# i2c_arduino.net
KiCad netlist of a schematic drawn in EAGLE
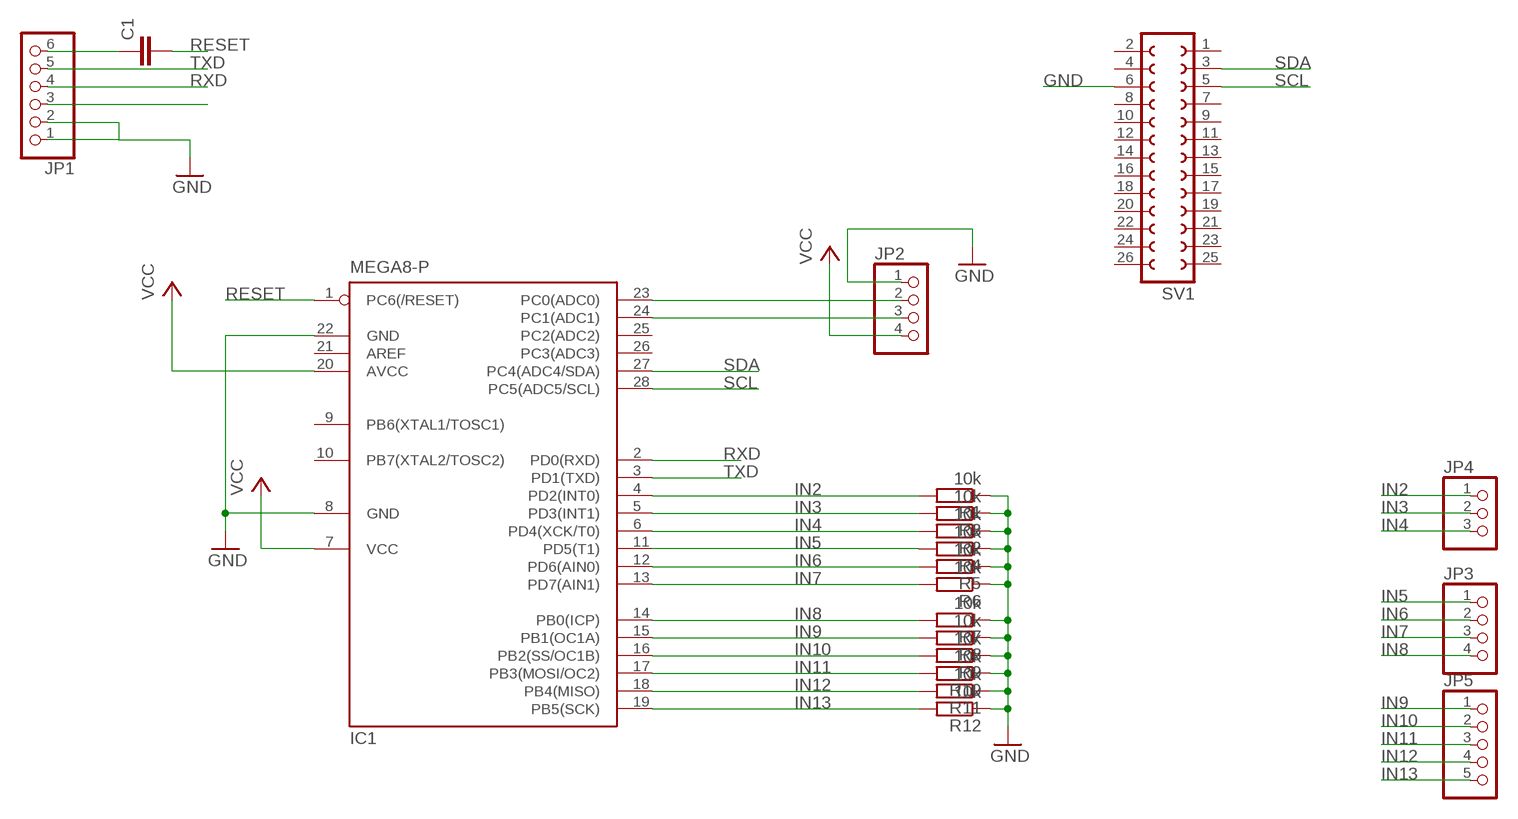
[diagram p0: schematic, sheet 1]

(export (version "E")
  (design (tool "Eeschema 10.0.6"))
  (components
    (comp (ref "C1")
      (value "C-EU025-025X050")
      (footprint "eagle-import:C025-025X050")
      (libsource (lib "eagle-import") (part "C-EU025-025X050"))
    )
    (comp (ref "IC1")
      (value "MEGA8-P")
      (footprint "eagle-import:DIL28-3")
      (libsource (lib "eagle-import") (part "MEGA8-P"))
    )
    (comp (ref "JP1")
      (value "PINHD-1X6/90")
      (footprint "eagle-import:1X06_90")
      (libsource (lib "eagle-import") (part "PINHD-1X6/90"))
    )
    (comp (ref "JP2")
      (value "PINHD-1X4")
      (footprint "eagle-import:1X04")
      (libsource (lib "eagle-import") (part "PINHD-1X4"))
    )
    (comp (ref "JP3")
      (value "PINHD-1X4")
      (footprint "eagle-import:1X04")
      (libsource (lib "eagle-import") (part "PINHD-1X4"))
    )
    (comp (ref "JP4")
      (value "PINHD-1X3")
      (footprint "eagle-import:1X03")
      (libsource (lib "eagle-import") (part "PINHD-1X3"))
    )
    (comp (ref "JP5")
      (value "PINHD-1X5")
      (footprint "eagle-import:1X05")
      (libsource (lib "eagle-import") (part "PINHD-1X5"))
    )
    (comp (ref "R1")
      (value "10k")
      (footprint "eagle-import:M1206")
      (libsource (lib "eagle-import") (part "R-EU_M1206"))
    )
    (comp (ref "R2")
      (value "10k")
      (footprint "eagle-import:M1206")
      (libsource (lib "eagle-import") (part "R-EU_M1206"))
    )
    (comp (ref "R3")
      (value "10k")
      (footprint "eagle-import:M1206")
      (libsource (lib "eagle-import") (part "R-EU_M1206"))
    )
    (comp (ref "R4")
      (value "10k")
      (footprint "eagle-import:M1206")
      (libsource (lib "eagle-import") (part "R-EU_M1206"))
    )
    (comp (ref "R5")
      (value "10k")
      (footprint "eagle-import:M1206")
      (libsource (lib "eagle-import") (part "R-EU_M1206"))
    )
    (comp (ref "R6")
      (value "10k")
      (footprint "eagle-import:M1206")
      (libsource (lib "eagle-import") (part "R-EU_M1206"))
    )
    (comp (ref "R7")
      (value "10k")
      (footprint "eagle-import:M1206")
      (libsource (lib "eagle-import") (part "R-EU_M1206"))
    )
    (comp (ref "R8")
      (value "10k")
      (footprint "eagle-import:M1206")
      (libsource (lib "eagle-import") (part "R-EU_M1206"))
    )
    (comp (ref "R9")
      (value "10k")
      (footprint "eagle-import:M1206")
      (libsource (lib "eagle-import") (part "R-EU_M1206"))
    )
    (comp (ref "R10")
      (value "10k")
      (footprint "eagle-import:M1206")
      (libsource (lib "eagle-import") (part "R-EU_M1206"))
    )
    (comp (ref "R11")
      (value "10k")
      (footprint "eagle-import:M1206")
      (libsource (lib "eagle-import") (part "R-EU_M1206"))
    )
    (comp (ref "R12")
      (value "10k")
      (footprint "eagle-import:M1206")
      (libsource (lib "eagle-import") (part "R-EU_M1206"))
    )
    (comp (ref "SV1")
      (value "FE13-2")
      (footprint "eagle-import:FE13-2")
      (libsource (lib "eagle-import") (part "FE13-2"))
    )
  )
  (nets
    (net (code "1") (name "/IN2") (class "Default")
      (node (ref "IC1") (pin "4") (pinfunction "PD2(INT0)_4") (pintype "bidirectional"))
      (node (ref "JP4") (pin "1") (pinfunction "1_1") (pintype "passive"))
      (node (ref "R1") (pin "2") (pinfunction "2_2") (pintype "passive"))
    )
    (net (code "2") (name "/IN3") (class "Default")
      (node (ref "IC1") (pin "5") (pinfunction "PD3(INT1)_5") (pintype "bidirectional"))
      (node (ref "JP4") (pin "2") (pinfunction "2_2") (pintype "passive"))
      (node (ref "R3") (pin "2") (pinfunction "2_2") (pintype "passive"))
    )
    (net (code "3") (name "/IN4") (class "Default")
      (node (ref "IC1") (pin "6") (pinfunction "PD4(XCK/T0)_6") (pintype "bidirectional"))
      (node (ref "JP4") (pin "3") (pinfunction "3_3") (pintype "passive"))
      (node (ref "R2") (pin "2") (pinfunction "2_2") (pintype "passive"))
    )
    (net (code "4") (name "/IN5") (class "Default")
      (node (ref "IC1") (pin "11") (pinfunction "PD5(T1)_11") (pintype "bidirectional"))
      (node (ref "JP3") (pin "1") (pinfunction "1_1") (pintype "passive"))
      (node (ref "R4") (pin "2") (pinfunction "2_2") (pintype "passive"))
    )
    (net (code "5") (name "/IN6") (class "Default")
      (node (ref "IC1") (pin "12") (pinfunction "PD6(AIN0)_12") (pintype "bidirectional"))
      (node (ref "JP3") (pin "2") (pinfunction "2_2") (pintype "passive"))
      (node (ref "R5") (pin "2") (pinfunction "2_2") (pintype "passive"))
    )
    (net (code "6") (name "/IN7") (class "Default")
      (node (ref "IC1") (pin "13") (pinfunction "PD7(AIN1)_13") (pintype "bidirectional"))
      (node (ref "JP3") (pin "3") (pinfunction "3_3") (pintype "passive"))
      (node (ref "R6") (pin "2") (pinfunction "2_2") (pintype "passive"))
    )
    (net (code "7") (name "/IN8") (class "Default")
      (node (ref "IC1") (pin "14") (pinfunction "PB0(ICP)_14") (pintype "bidirectional"))
      (node (ref "JP3") (pin "4") (pinfunction "4_4") (pintype "passive"))
      (node (ref "R7") (pin "2") (pinfunction "2_2") (pintype "passive"))
    )
    (net (code "8") (name "/IN9") (class "Default")
      (node (ref "IC1") (pin "15") (pinfunction "PB1(OC1A)_15") (pintype "bidirectional"))
      (node (ref "JP5") (pin "1") (pinfunction "1_1") (pintype "passive"))
      (node (ref "R8") (pin "2") (pinfunction "2_2") (pintype "passive"))
    )
    (net (code "9") (name "/IN10") (class "Default")
      (node (ref "IC1") (pin "16") (pinfunction "PB2(SS/OC1B)_16") (pintype "bidirectional"))
      (node (ref "JP5") (pin "2") (pinfunction "2_2") (pintype "passive"))
      (node (ref "R9") (pin "2") (pinfunction "2_2") (pintype "passive"))
    )
    (net (code "10") (name "/IN11") (class "Default")
      (node (ref "IC1") (pin "17") (pinfunction "PB3(MOSI/OC2)_17") (pintype "bidirectional"))
      (node (ref "JP5") (pin "3") (pinfunction "3_3") (pintype "passive"))
      (node (ref "R10") (pin "2") (pinfunction "2_2") (pintype "passive"))
    )
    (net (code "11") (name "/IN12") (class "Default")
      (node (ref "IC1") (pin "18") (pinfunction "PB4(MISO)_18") (pintype "bidirectional"))
      (node (ref "JP5") (pin "4") (pinfunction "4_4") (pintype "passive"))
      (node (ref "R11") (pin "2") (pinfunction "2_2") (pintype "passive"))
    )
    (net (code "12") (name "/IN13") (class "Default")
      (node (ref "IC1") (pin "19") (pinfunction "PB5(SCK)_19") (pintype "bidirectional"))
      (node (ref "JP5") (pin "5") (pinfunction "5_5") (pintype "passive"))
      (node (ref "R12") (pin "2") (pinfunction "2_2") (pintype "passive"))
    )
    (net (code "13") (name "/RESET") (class "Default")
      (node (ref "C1") (pin "2") (pinfunction "2_2") (pintype "passive"))
      (node (ref "IC1") (pin "1") (pinfunction "PC6(/RESET)_1") (pintype "bidirectional"))
    )
    (net (code "14") (name "/RXD") (class "Default")
      (node (ref "IC1") (pin "2") (pinfunction "PD0(RXD)_2") (pintype "bidirectional"))
      (node (ref "JP1") (pin "4") (pinfunction "4_4") (pintype "passive"))
    )
    (net (code "15") (name "/SCL") (class "Default")
      (node (ref "IC1") (pin "28") (pinfunction "PC5(ADC5/SCL)_28") (pintype "bidirectional"))
      (node (ref "SV1") (pin "5") (pinfunction "5_5") (pintype "passive"))
    )
    (net (code "16") (name "/SDA") (class "Default")
      (node (ref "IC1") (pin "27") (pinfunction "PC4(ADC4/SDA)_27") (pintype "bidirectional"))
      (node (ref "SV1") (pin "3") (pinfunction "3_3") (pintype "passive"))
    )
    (net (code "17") (name "/TXD") (class "Default")
      (node (ref "IC1") (pin "3") (pinfunction "PD1(TXD)_3") (pintype "bidirectional"))
      (node (ref "JP1") (pin "5") (pinfunction "5_5") (pintype "passive"))
    )
    (net (code "18") (name "GND") (class "Default")
      (node (ref "IC1") (pin "22") (pinfunction "GND_22") (pintype "power_in"))
      (node (ref "IC1") (pin "8") (pinfunction "GND_8") (pintype "power_in"))
      (node (ref "JP1") (pin "1") (pinfunction "1_1") (pintype "passive"))
      (node (ref "JP1") (pin "2") (pinfunction "2_2") (pintype "passive"))
      (node (ref "JP2") (pin "1") (pinfunction "1_1") (pintype "passive"))
      (node (ref "R1") (pin "1") (pinfunction "1_1") (pintype "passive"))
      (node (ref "R10") (pin "1") (pinfunction "1_1") (pintype "passive"))
      (node (ref "R11") (pin "1") (pinfunction "1_1") (pintype "passive"))
      (node (ref "R12") (pin "1") (pinfunction "1_1") (pintype "passive"))
      (node (ref "R2") (pin "1") (pinfunction "1_1") (pintype "passive"))
      (node (ref "R3") (pin "1") (pinfunction "1_1") (pintype "passive"))
      (node (ref "R4") (pin "1") (pinfunction "1_1") (pintype "passive"))
      (node (ref "R5") (pin "1") (pinfunction "1_1") (pintype "passive"))
      (node (ref "R6") (pin "1") (pinfunction "1_1") (pintype "passive"))
      (node (ref "R7") (pin "1") (pinfunction "1_1") (pintype "passive"))
      (node (ref "R8") (pin "1") (pinfunction "1_1") (pintype "passive"))
      (node (ref "R9") (pin "1") (pinfunction "1_1") (pintype "passive"))
      (node (ref "SV1") (pin "6") (pinfunction "6_6") (pintype "passive"))
    )
    (net (code "19") (name "Net-(C1-Pad1)") (class "Default")
      (node (ref "C1") (pin "1") (pinfunction "1_1") (pintype "passive"))
      (node (ref "JP1") (pin "6") (pinfunction "6_6") (pintype "passive"))
    )
    (net (code "20") (name "Net-(IC1-PC0(ADC0))") (class "Default")
      (node (ref "IC1") (pin "23") (pinfunction "PC0(ADC0)_23") (pintype "bidirectional"))
      (node (ref "JP2") (pin "2") (pinfunction "2_2") (pintype "passive"))
    )
    (net (code "21") (name "Net-(IC1-PC1(ADC1))") (class "Default")
      (node (ref "IC1") (pin "24") (pinfunction "PC1(ADC1)_24") (pintype "bidirectional"))
      (node (ref "JP2") (pin "3") (pinfunction "3_3") (pintype "passive"))
    )
    (net (code "22") (name "VCC") (class "Default")
      (node (ref "IC1") (pin "20") (pinfunction "AVCC_20") (pintype "power_in"))
      (node (ref "IC1") (pin "7") (pinfunction "VCC_7") (pintype "power_in"))
      (node (ref "JP1") (pin "3") (pinfunction "3_3") (pintype "passive"))
      (node (ref "JP2") (pin "4") (pinfunction "4_4") (pintype "passive"))
    )
    (net (code "23") (name "unconnected-(IC1-AREF-Pad21)") (class "Default")
      (node (ref "IC1") (pin "21") (pinfunction "AREF_21") (pintype "passive"))
    )
    (net (code "24") (name "unconnected-(IC1-PB6(XTAL1{slash}TOSC1)-Pad9)") (class "Default")
      (node (ref "IC1") (pin "9") (pinfunction "PB6(XTAL1/TOSC1)_9") (pintype "bidirectional"))
    )
    (net (code "25") (name "unconnected-(IC1-PB7(XTAL2{slash}TOSC2)-Pad10)") (class "Default")
      (node (ref "IC1") (pin "10") (pinfunction "PB7(XTAL2/TOSC2)_10") (pintype "bidirectional"))
    )
    (net (code "26") (name "unconnected-(IC1-PC2(ADC2)-Pad25)") (class "Default")
      (node (ref "IC1") (pin "25") (pinfunction "PC2(ADC2)_25") (pintype "bidirectional"))
    )
    (net (code "27") (name "unconnected-(IC1-PC3(ADC3)-Pad26)") (class "Default")
      (node (ref "IC1") (pin "26") (pinfunction "PC3(ADC3)_26") (pintype "bidirectional"))
    )
    (net (code "28") (name "unconnected-(SV1-Pad1)") (class "Default")
      (node (ref "SV1") (pin "1") (pinfunction "1_1") (pintype "passive"))
    )
    (net (code "29") (name "unconnected-(SV1-Pad2)") (class "Default")
      (node (ref "SV1") (pin "2") (pinfunction "2_2") (pintype "passive"))
    )
    (net (code "30") (name "unconnected-(SV1-Pad4)") (class "Default")
      (node (ref "SV1") (pin "4") (pinfunction "4_4") (pintype "passive"))
    )
    (net (code "31") (name "unconnected-(SV1-Pad7)") (class "Default")
      (node (ref "SV1") (pin "7") (pinfunction "7_7") (pintype "passive"))
    )
    (net (code "32") (name "unconnected-(SV1-Pad8)") (class "Default")
      (node (ref "SV1") (pin "8") (pinfunction "8_8") (pintype "passive"))
    )
    (net (code "33") (name "unconnected-(SV1-Pad9)") (class "Default")
      (node (ref "SV1") (pin "9") (pinfunction "9_9") (pintype "passive"))
    )
    (net (code "34") (name "unconnected-(SV1-Pad10)") (class "Default")
      (node (ref "SV1") (pin "10") (pinfunction "10_10") (pintype "passive"))
    )
    (net (code "35") (name "unconnected-(SV1-Pad11)") (class "Default")
      (node (ref "SV1") (pin "11") (pinfunction "11_11") (pintype "passive"))
    )
    (net (code "36") (name "unconnected-(SV1-Pad12)") (class "Default")
      (node (ref "SV1") (pin "12") (pinfunction "12_12") (pintype "passive"))
    )
    (net (code "37") (name "unconnected-(SV1-Pad13)") (class "Default")
      (node (ref "SV1") (pin "13") (pinfunction "13_13") (pintype "passive"))
    )
    (net (code "38") (name "unconnected-(SV1-Pad14)") (class "Default")
      (node (ref "SV1") (pin "14") (pinfunction "14_14") (pintype "passive"))
    )
    (net (code "39") (name "unconnected-(SV1-Pad15)") (class "Default")
      (node (ref "SV1") (pin "15") (pinfunction "15_15") (pintype "passive"))
    )
    (net (code "40") (name "unconnected-(SV1-Pad16)") (class "Default")
      (node (ref "SV1") (pin "16") (pinfunction "16_16") (pintype "passive"))
    )
    (net (code "41") (name "unconnected-(SV1-Pad17)") (class "Default")
      (node (ref "SV1") (pin "17") (pinfunction "17_17") (pintype "passive"))
    )
    (net (code "42") (name "unconnected-(SV1-Pad18)") (class "Default")
      (node (ref "SV1") (pin "18") (pinfunction "18_18") (pintype "passive"))
    )
    (net (code "43") (name "unconnected-(SV1-Pad19)") (class "Default")
      (node (ref "SV1") (pin "19") (pinfunction "19_19") (pintype "passive"))
    )
    (net (code "44") (name "unconnected-(SV1-Pad20)") (class "Default")
      (node (ref "SV1") (pin "20") (pinfunction "20_20") (pintype "passive"))
    )
    (net (code "45") (name "unconnected-(SV1-Pad21)") (class "Default")
      (node (ref "SV1") (pin "21") (pinfunction "21_21") (pintype "passive"))
    )
    (net (code "46") (name "unconnected-(SV1-Pad22)") (class "Default")
      (node (ref "SV1") (pin "22") (pinfunction "22_22") (pintype "passive"))
    )
    (net (code "47") (name "unconnected-(SV1-Pad23)") (class "Default")
      (node (ref "SV1") (pin "23") (pinfunction "23_23") (pintype "passive"))
    )
    (net (code "48") (name "unconnected-(SV1-Pad24)") (class "Default")
      (node (ref "SV1") (pin "24") (pinfunction "24_24") (pintype "passive"))
    )
    (net (code "49") (name "unconnected-(SV1-Pad25)") (class "Default")
      (node (ref "SV1") (pin "25") (pinfunction "25_25") (pintype "passive"))
    )
    (net (code "50") (name "unconnected-(SV1-Pad26)") (class "Default")
      (node (ref "SV1") (pin "26") (pinfunction "26_26") (pintype "passive"))
    )
  )
)
